# ZeroCrossDetection.net
KiCad netlist of a schematic drawn in Altium Designer
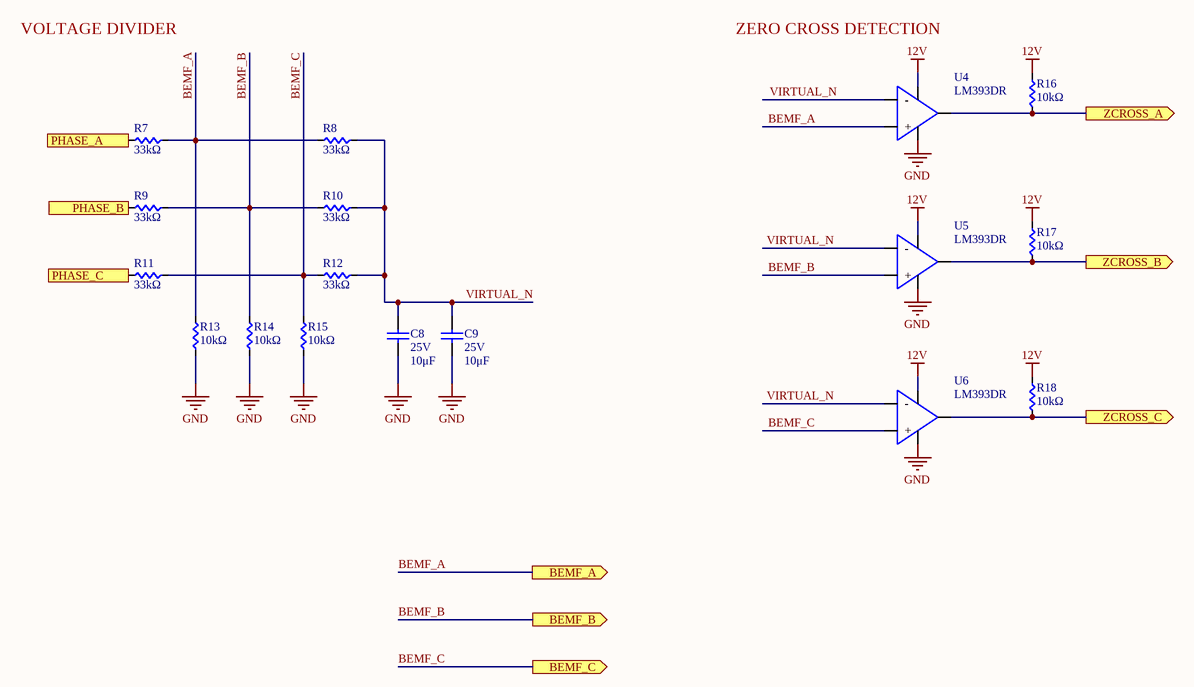
[diagram p0: ZeroCrossDetection.SchDoc]

(export (version "E")
  (design (tool "Eeschema 10.0.6"))
  (components
    (comp (ref "C8")
      (value "10μF")
      (footprint "CAP0603")
      (description "CAP CER 10UF 25V X5R 0603")
      (fields (field (name "VOLTAGE RATING") "25V") (field (name "Comment") "GRM188R61E106MA73J"))
      (libsource (lib "BLDC_Schematic_Library") (part "GRM188R61E106MA73J"))
    )
    (comp (ref "C9")
      (value "10μF")
      (footprint "CAP0603")
      (description "CAP CER 10UF 25V X5R 0603")
      (fields (field (name "VOLTAGE RATING") "25V") (field (name "Comment") "GRM188R61E106MA73J"))
      (libsource (lib "BLDC_Schematic_Library") (part "GRM188R61E106MA73J"))
    )
    (comp (ref "R7")
      (value "33kΩ")
      (footprint "RES0603")
      (description "RES SMD 33K OHM 0.1% 1/10W 0603")
      (fields (field (name "Comment") "RT0603BRD0733KL"))
      (libsource (lib "BLDC_Schematic_Library") (part "RT0603BRD0733KL"))
    )
    (comp (ref "R8")
      (value "33kΩ")
      (footprint "RES0603")
      (description "RES SMD 33K OHM 0.1% 1/10W 0603")
      (fields (field (name "Comment") "RT0603BRD0733KL"))
      (libsource (lib "BLDC_Schematic_Library") (part "RT0603BRD0733KL"))
    )
    (comp (ref "R9")
      (value "33kΩ")
      (footprint "RES0603")
      (description "RES SMD 33K OHM 0.1% 1/10W 0603")
      (fields (field (name "Comment") "RT0603BRD0733KL"))
      (libsource (lib "BLDC_Schematic_Library") (part "RT0603BRD0733KL"))
    )
    (comp (ref "R10")
      (value "33kΩ")
      (footprint "RES0603")
      (description "RES SMD 33K OHM 0.1% 1/10W 0603")
      (fields (field (name "Comment") "RT0603BRD0733KL"))
      (libsource (lib "BLDC_Schematic_Library") (part "RT0603BRD0733KL"))
    )
    (comp (ref "R11")
      (value "33kΩ")
      (footprint "RES0603")
      (description "RES SMD 33K OHM 0.1% 1/10W 0603")
      (fields (field (name "Comment") "RT0603BRD0733KL"))
      (libsource (lib "BLDC_Schematic_Library") (part "RT0603BRD0733KL"))
    )
    (comp (ref "R12")
      (value "33kΩ")
      (footprint "RES0603")
      (description "RES SMD 33K OHM 0.1% 1/10W 0603")
      (fields (field (name "Comment") "RT0603BRD0733KL"))
      (libsource (lib "BLDC_Schematic_Library") (part "RT0603BRD0733KL"))
    )
    (comp (ref "R13")
      (value "10kΩ")
      (footprint "RES0402")
      (description "RES 10K OHM 5% 1/16W 0402")
      (fields (field (name "Comment") "RC0402JR-0710KL"))
      (libsource (lib "BLDC_Schematic_Library") (part "RC0402JR-0710KL"))
    )
    (comp (ref "R14")
      (value "10kΩ")
      (footprint "RES0402")
      (description "RES 10K OHM 5% 1/16W 0402")
      (fields (field (name "Comment") "RC0402JR-0710KL"))
      (libsource (lib "BLDC_Schematic_Library") (part "RC0402JR-0710KL"))
    )
    (comp (ref "R15")
      (value "10kΩ")
      (footprint "RES0402")
      (description "RES 10K OHM 5% 1/16W 0402")
      (fields (field (name "Comment") "RC0402JR-0710KL"))
      (libsource (lib "BLDC_Schematic_Library") (part "RC0402JR-0710KL"))
    )
    (comp (ref "R16")
      (value "10kΩ")
      (footprint "RES0402")
      (description "RES 10K OHM 5% 1/16W 0402")
      (fields (field (name "Comment") "RC0402JR-0710KL"))
      (libsource (lib "BLDC_Schematic_Library") (part "RC0402JR-0710KL"))
    )
    (comp (ref "R17")
      (value "10kΩ")
      (footprint "RES0402")
      (description "RES 10K OHM 5% 1/16W 0402")
      (fields (field (name "Comment") "RC0402JR-0710KL"))
      (libsource (lib "BLDC_Schematic_Library") (part "RC0402JR-0710KL"))
    )
    (comp (ref "R18")
      (value "10kΩ")
      (footprint "RES0402")
      (description "RES 10K OHM 5% 1/16W 0402")
      (fields (field (name "Comment") "RC0402JR-0710KL"))
      (libsource (lib "BLDC_Schematic_Library") (part "RC0402JR-0710KL"))
    )
    (comp (ref "U4")
      (value "LM393DR")
      (footprint "SOT25")
      (fields (field (name "MANUFACTURER") "Texas Instruments"))
      (libsource (lib "BLDC_Schematic_Library") (part "LM393DR"))
    )
    (comp (ref "U5")
      (value "LM393DR")
      (footprint "SOT25")
      (fields (field (name "MANUFACTURER") "Texas Instruments"))
      (libsource (lib "BLDC_Schematic_Library") (part "LM393DR"))
    )
    (comp (ref "U6")
      (value "LM393DR")
      (footprint "SOT25")
      (fields (field (name "MANUFACTURER") "Texas Instruments"))
      (libsource (lib "BLDC_Schematic_Library") (part "LM393DR"))
    )
  )
  (nets
    (net (code "1") (name "/BEMF_A") (class "Default")
      (node (ref "R13") (pin "1") (pinfunction "1_1") (pintype "passive"))
      (node (ref "R7") (pin "2") (pinfunction "2_2") (pintype "passive"))
      (node (ref "R8") (pin "1") (pinfunction "1_1") (pintype "passive"))
      (node (ref "U4") (pin "3") (pinfunction "+_3") (pintype "passive"))
    )
    (net (code "2") (name "/BEMF_B") (class "Default")
      (node (ref "R10") (pin "1") (pinfunction "1_1") (pintype "passive"))
      (node (ref "R14") (pin "1") (pinfunction "1_1") (pintype "passive"))
      (node (ref "R9") (pin "2") (pinfunction "2_2") (pintype "passive"))
      (node (ref "U5") (pin "3") (pinfunction "+_3") (pintype "passive"))
    )
    (net (code "3") (name "/BEMF_C") (class "Default")
      (node (ref "R11") (pin "2") (pinfunction "2_2") (pintype "passive"))
      (node (ref "R12") (pin "1") (pinfunction "1_1") (pintype "passive"))
      (node (ref "R15") (pin "1") (pinfunction "1_1") (pintype "passive"))
      (node (ref "U6") (pin "3") (pinfunction "+_3") (pintype "passive"))
    )
    (net (code "4") (name "/PHASE_A") (class "Default")
      (node (ref "R7") (pin "1") (pinfunction "1_1") (pintype "passive"))
    )
    (net (code "5") (name "/PHASE_B") (class "Default")
      (node (ref "R9") (pin "1") (pinfunction "1_1") (pintype "passive"))
    )
    (net (code "6") (name "/PHASE_C") (class "Default")
      (node (ref "R11") (pin "1") (pinfunction "1_1") (pintype "passive"))
    )
    (net (code "7") (name "/VIRTUAL_N") (class "Default")
      (node (ref "C8") (pin "1") (pinfunction "1_1") (pintype "passive"))
      (node (ref "C9") (pin "1") (pinfunction "1_1") (pintype "passive"))
      (node (ref "R10") (pin "2") (pinfunction "2_2") (pintype "passive"))
      (node (ref "R12") (pin "2") (pinfunction "2_2") (pintype "passive"))
      (node (ref "R8") (pin "2") (pinfunction "2_2") (pintype "passive"))
      (node (ref "U4") (pin "1") (pinfunction "-_1") (pintype "passive"))
      (node (ref "U5") (pin "1") (pinfunction "-_1") (pintype "passive"))
      (node (ref "U6") (pin "1") (pinfunction "-_1") (pintype "passive"))
    )
    (net (code "8") (name "/ZCROSS_A") (class "Default")
      (node (ref "R16") (pin "1") (pinfunction "1_1") (pintype "passive"))
      (node (ref "U4") (pin "4") (pinfunction "VOUT_4") (pintype "passive"))
    )
    (net (code "9") (name "/ZCROSS_B") (class "Default")
      (node (ref "R17") (pin "1") (pinfunction "1_1") (pintype "passive"))
      (node (ref "U5") (pin "4") (pinfunction "VOUT_4") (pintype "passive"))
    )
    (net (code "10") (name "/ZCROSS_C") (class "Default")
      (node (ref "R18") (pin "1") (pinfunction "1_1") (pintype "passive"))
      (node (ref "U6") (pin "4") (pinfunction "VOUT_4") (pintype "passive"))
    )
    (net (code "11") (name "12V") (class "Default")
      (node (ref "R16") (pin "2") (pinfunction "2_2") (pintype "passive"))
      (node (ref "R17") (pin "2") (pinfunction "2_2") (pintype "passive"))
      (node (ref "R18") (pin "2") (pinfunction "2_2") (pintype "passive"))
      (node (ref "U4") (pin "5") (pinfunction "VCC_5") (pintype "passive"))
      (node (ref "U5") (pin "5") (pinfunction "VCC_5") (pintype "passive"))
      (node (ref "U6") (pin "5") (pinfunction "VCC_5") (pintype "passive"))
    )
    (net (code "12") (name "GND") (class "Default")
      (node (ref "C8") (pin "2") (pinfunction "2_2") (pintype "passive"))
      (node (ref "C9") (pin "2") (pinfunction "2_2") (pintype "passive"))
      (node (ref "R13") (pin "2") (pinfunction "2_2") (pintype "passive"))
      (node (ref "R14") (pin "2") (pinfunction "2_2") (pintype "passive"))
      (node (ref "R15") (pin "2") (pinfunction "2_2") (pintype "passive"))
      (node (ref "U4") (pin "2") (pinfunction "GND_2") (pintype "passive"))
      (node (ref "U5") (pin "2") (pinfunction "GND_2") (pintype "passive"))
      (node (ref "U6") (pin "2") (pinfunction "GND_2") (pintype "passive"))
    )
  )
)
